# Precision_Leonardo_Charlieplex_2_0.net
KiCad netlist of a schematic drawn in EAGLE
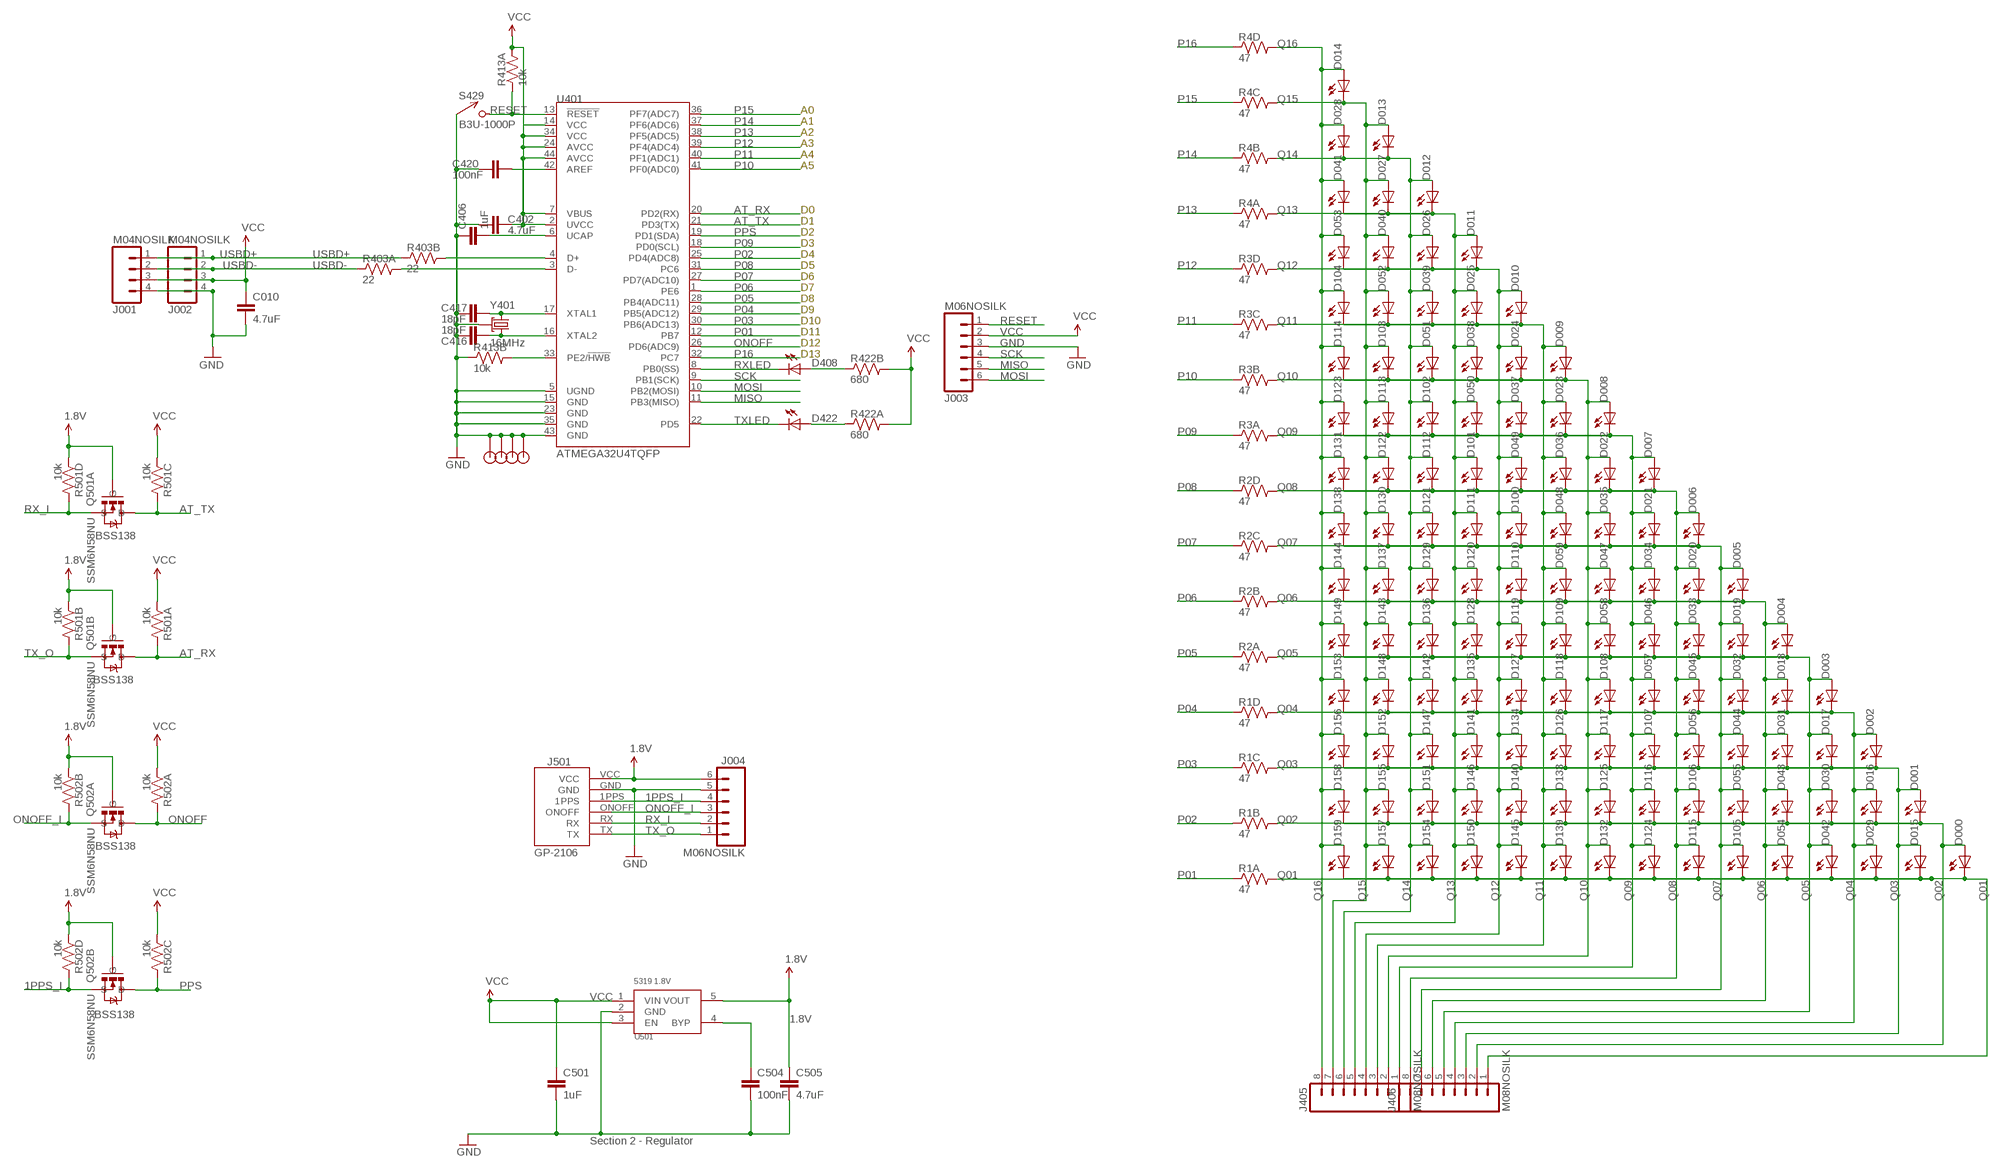
[diagram p0: schematic, sheet 1]

(export (version "E")
  (design (tool "Eeschema 10.0.6"))
  (components
    (comp (ref "C010")
      (value "4.7uF")
      (footprint "eagle-import:0603-CAP")
      (libsource (lib "eagle-import") (part "CAP0603-CAP"))
    )
    (comp (ref "C402")
      (value "4.7uF")
      (footprint "eagle-import:0603-CAP")
      (libsource (lib "eagle-import") (part "CAP0603-CAP"))
    )
    (comp (ref "C406")
      (value "1uF")
      (footprint "eagle-import:0603-CAP")
      (libsource (lib "eagle-import") (part "SparkFun-Passives_CAP0603-CAP"))
    )
    (comp (ref "C416")
      (value "18pF")
      (footprint "eagle-import:0603-CAP")
      (libsource (lib "eagle-import") (part "CAP0603-CAP"))
    )
    (comp (ref "C417")
      (value "18pF")
      (footprint "eagle-import:0603-CAP")
      (libsource (lib "eagle-import") (part "CAP0603-CAP"))
    )
    (comp (ref "C420")
      (value "100nF")
      (footprint "eagle-import:0603-CAP")
      (libsource (lib "eagle-import") (part "CAP0603-CAP"))
    )
    (comp (ref "C501")
      (value "1uF")
      (footprint "eagle-import:0603-CAP")
      (libsource (lib "eagle-import") (part "SparkFun-Passives_CAP0603-CAP"))
    )
    (comp (ref "C504")
      (value "100nF")
      (footprint "eagle-import:0603-CAP")
      (libsource (lib "eagle-import") (part "SparkFun-Passives_CAP0603-CAP"))
    )
    (comp (ref "C505")
      (value "4.7uF")
      (footprint "eagle-import:0603-CAP")
      (libsource (lib "eagle-import") (part "SparkFun-Passives_CAP0603-CAP"))
    )
    (comp (ref "D000")
      (value "HOUR")
      (footprint "eagle-import:LED-0603")
      (libsource (lib "eagle-import") (part "LED0603"))
    )
    (comp (ref "D001")
      (value "HOUR")
      (footprint "eagle-import:LED-0603")
      (libsource (lib "eagle-import") (part "LED0603"))
    )
    (comp (ref "D002")
      (value "HOUR")
      (footprint "eagle-import:LED-0603")
      (libsource (lib "eagle-import") (part "LED0603"))
    )
    (comp (ref "D003")
      (value "HOUR")
      (footprint "eagle-import:LED-0603")
      (libsource (lib "eagle-import") (part "LED0603"))
    )
    (comp (ref "D004")
      (value "HOUR")
      (footprint "eagle-import:LED-0603")
      (libsource (lib "eagle-import") (part "LED0603"))
    )
    (comp (ref "D005")
      (value "HOUR")
      (footprint "eagle-import:LED-0603")
      (libsource (lib "eagle-import") (part "LED0603"))
    )
    (comp (ref "D006")
      (value "HOUR")
      (footprint "eagle-import:LED-0603")
      (libsource (lib "eagle-import") (part "LED0603"))
    )
    (comp (ref "D007")
      (value "HOUR")
      (footprint "eagle-import:LED-0603")
      (libsource (lib "eagle-import") (part "LED0603"))
    )
    (comp (ref "D008")
      (value "HOUR")
      (footprint "eagle-import:LED-0603")
      (libsource (lib "eagle-import") (part "LED0603"))
    )
    (comp (ref "D009")
      (value "HOUR")
      (footprint "eagle-import:LED-0603")
      (libsource (lib "eagle-import") (part "LED0603"))
    )
    (comp (ref "D010")
      (value "HOUR")
      (footprint "eagle-import:LED-0603")
      (libsource (lib "eagle-import") (part "LED0603"))
    )
    (comp (ref "D011")
      (value "HOUR")
      (footprint "eagle-import:LED-0603")
      (libsource (lib "eagle-import") (part "LED0603"))
    )
    (comp (ref "D012")
      (value "HOUR")
      (footprint "eagle-import:LED-0603")
      (libsource (lib "eagle-import") (part "LED0603"))
    )
    (comp (ref "D013")
      (value "HOUR")
      (footprint "eagle-import:LED-0603")
      (libsource (lib "eagle-import") (part "LED0603"))
    )
    (comp (ref "D014")
      (value "HOUR")
      (footprint "eagle-import:LED-0603")
      (libsource (lib "eagle-import") (part "LED0603"))
    )
    (comp (ref "D015")
      (value "HOUR")
      (footprint "eagle-import:LED-0603")
      (libsource (lib "eagle-import") (part "LED0603"))
    )
    (comp (ref "D016")
      (value "HOUR")
      (footprint "eagle-import:LED-0603")
      (libsource (lib "eagle-import") (part "LED0603"))
    )
    (comp (ref "D017")
      (value "HOUR")
      (footprint "eagle-import:LED-0603")
      (libsource (lib "eagle-import") (part "LED0603"))
    )
    (comp (ref "D018")
      (value "HOUR")
      (footprint "eagle-import:LED-0603")
      (libsource (lib "eagle-import") (part "LED0603"))
    )
    (comp (ref "D019")
      (value "HOUR")
      (footprint "eagle-import:LED-0603")
      (libsource (lib "eagle-import") (part "LED0603"))
    )
    (comp (ref "D020")
      (value "HOUR")
      (footprint "eagle-import:LED-0603")
      (libsource (lib "eagle-import") (part "LED0603"))
    )
    (comp (ref "D021")
      (value "HOUR")
      (footprint "eagle-import:LED-0603")
      (libsource (lib "eagle-import") (part "LED0603"))
    )
    (comp (ref "D022")
      (value "HOUR")
      (footprint "eagle-import:LED-0603")
      (libsource (lib "eagle-import") (part "LED0603"))
    )
    (comp (ref "D023")
      (value "HOUR")
      (footprint "eagle-import:LED-0603")
      (libsource (lib "eagle-import") (part "LED0603"))
    )
    (comp (ref "D024")
      (value "HOUR")
      (footprint "eagle-import:LED-0603")
      (libsource (lib "eagle-import") (part "LED0603"))
    )
    (comp (ref "D025")
      (value "HOUR")
      (footprint "eagle-import:LED-0603")
      (libsource (lib "eagle-import") (part "LED0603"))
    )
    (comp (ref "D026")
      (value "HOUR")
      (footprint "eagle-import:LED-0603")
      (libsource (lib "eagle-import") (part "LED0603"))
    )
    (comp (ref "D027")
      (value "HOUR")
      (footprint "eagle-import:LED-0603")
      (libsource (lib "eagle-import") (part "LED0603"))
    )
    (comp (ref "D028")
      (value "HOUR")
      (footprint "eagle-import:LED-0603")
      (libsource (lib "eagle-import") (part "LED0603"))
    )
    (comp (ref "D029")
      (value "HOUR")
      (footprint "eagle-import:LED-0603")
      (libsource (lib "eagle-import") (part "LED0603"))
    )
    (comp (ref "D030")
      (value "HOUR")
      (footprint "eagle-import:LED-0603")
      (libsource (lib "eagle-import") (part "LED0603"))
    )
    (comp (ref "D031")
      (value "HOUR")
      (footprint "eagle-import:LED-0603")
      (libsource (lib "eagle-import") (part "LED0603"))
    )
    (comp (ref "D032")
      (value "HOUR")
      (footprint "eagle-import:LED-0603")
      (libsource (lib "eagle-import") (part "LED0603"))
    )
    (comp (ref "D033")
      (value "HOUR")
      (footprint "eagle-import:LED-0603")
      (libsource (lib "eagle-import") (part "LED0603"))
    )
    (comp (ref "D034")
      (value "HOUR")
      (footprint "eagle-import:LED-0603")
      (libsource (lib "eagle-import") (part "LED0603"))
    )
    (comp (ref "D035")
      (value "HOUR")
      (footprint "eagle-import:LED-0603")
      (libsource (lib "eagle-import") (part "LED0603"))
    )
    (comp (ref "D036")
      (value "HOUR")
      (footprint "eagle-import:LED-0603")
      (libsource (lib "eagle-import") (part "LED0603"))
    )
    (comp (ref "D037")
      (value "HOUR")
      (footprint "eagle-import:LED-0603")
      (libsource (lib "eagle-import") (part "LED0603"))
    )
    (comp (ref "D038")
      (value "HOUR")
      (footprint "eagle-import:LED-0603")
      (libsource (lib "eagle-import") (part "LED0603"))
    )
    (comp (ref "D039")
      (value "HOUR")
      (footprint "eagle-import:LED-0603")
      (libsource (lib "eagle-import") (part "LED0603"))
    )
    (comp (ref "D040")
      (value "HOUR")
      (footprint "eagle-import:LED-0603")
      (libsource (lib "eagle-import") (part "LED0603"))
    )
    (comp (ref "D041")
      (value "HOUR")
      (footprint "eagle-import:LED-0603")
      (libsource (lib "eagle-import") (part "LED0603"))
    )
    (comp (ref "D042")
      (value "HOUR")
      (footprint "eagle-import:LED-0603")
      (libsource (lib "eagle-import") (part "LED0603"))
    )
    (comp (ref "D043")
      (value "HOUR")
      (footprint "eagle-import:LED-0603")
      (libsource (lib "eagle-import") (part "LED0603"))
    )
    (comp (ref "D044")
      (value "HOUR")
      (footprint "eagle-import:LED-0603")
      (libsource (lib "eagle-import") (part "LED0603"))
    )
    (comp (ref "D045")
      (value "HOUR")
      (footprint "eagle-import:LED-0603")
      (libsource (lib "eagle-import") (part "LED0603"))
    )
    (comp (ref "D046")
      (value "HOUR")
      (footprint "eagle-import:LED-0603")
      (libsource (lib "eagle-import") (part "LED0603"))
    )
    (comp (ref "D047")
      (value "HOUR")
      (footprint "eagle-import:LED-0603")
      (libsource (lib "eagle-import") (part "LED0603"))
    )
    (comp (ref "D048")
      (value "HOUR")
      (footprint "eagle-import:LED-0603")
      (libsource (lib "eagle-import") (part "LED0603"))
    )
    (comp (ref "D049")
      (value "HOUR")
      (footprint "eagle-import:LED-0603")
      (libsource (lib "eagle-import") (part "LED0603"))
    )
    (comp (ref "D050")
      (value "HOUR")
      (footprint "eagle-import:LED-0603")
      (libsource (lib "eagle-import") (part "LED0603"))
    )
    (comp (ref "D051")
      (value "HOUR")
      (footprint "eagle-import:LED-0603")
      (libsource (lib "eagle-import") (part "LED0603"))
    )
    (comp (ref "D052")
      (value "HOUR")
      (footprint "eagle-import:LED-0603")
      (libsource (lib "eagle-import") (part "LED0603"))
    )
    (comp (ref "D053")
      (value "HOUR")
      (footprint "eagle-import:LED-0603")
      (libsource (lib "eagle-import") (part "LED0603"))
    )
    (comp (ref "D054")
      (value "HOUR")
      (footprint "eagle-import:LED-0603")
      (libsource (lib "eagle-import") (part "LED0603"))
    )
    (comp (ref "D055")
      (value "HOUR")
      (footprint "eagle-import:LED-0603")
      (libsource (lib "eagle-import") (part "LED0603"))
    )
    (comp (ref "D056")
      (value "HOUR")
      (footprint "eagle-import:LED-0603")
      (libsource (lib "eagle-import") (part "LED0603"))
    )
    (comp (ref "D057")
      (value "HOUR")
      (footprint "eagle-import:LED-0603")
      (libsource (lib "eagle-import") (part "LED0603"))
    )
    (comp (ref "D058")
      (value "HOUR")
      (footprint "eagle-import:LED-0603")
      (libsource (lib "eagle-import") (part "LED0603"))
    )
    (comp (ref "D059")
      (value "HOUR")
      (footprint "eagle-import:LED-0603")
      (libsource (lib "eagle-import") (part "LED0603"))
    )
    (comp (ref "D100")
      (value "HOUR")
      (footprint "eagle-import:LED-0603")
      (libsource (lib "eagle-import") (part "LED0603"))
    )
    (comp (ref "D101")
      (value "HOUR")
      (footprint "eagle-import:LED-0603")
      (libsource (lib "eagle-import") (part "LED0603"))
    )
    (comp (ref "D102")
      (value "HOUR")
      (footprint "eagle-import:LED-0603")
      (libsource (lib "eagle-import") (part "LED0603"))
    )
    (comp (ref "D103")
      (value "HOUR")
      (footprint "eagle-import:LED-0603")
      (libsource (lib "eagle-import") (part "LED0603"))
    )
    (comp (ref "D104")
      (value "HOUR")
      (footprint "eagle-import:LED-0603")
      (libsource (lib "eagle-import") (part "LED0603"))
    )
    (comp (ref "D105")
      (value "HOUR")
      (footprint "eagle-import:LED-0603")
      (libsource (lib "eagle-import") (part "LED0603"))
    )
    (comp (ref "D106")
      (value "HOUR")
      (footprint "eagle-import:LED-0603")
      (libsource (lib "eagle-import") (part "LED0603"))
    )
    (comp (ref "D107")
      (value "HOUR")
      (footprint "eagle-import:LED-0603")
      (libsource (lib "eagle-import") (part "LED0603"))
    )
    (comp (ref "D108")
      (value "HOUR")
      (footprint "eagle-import:LED-0603")
      (libsource (lib "eagle-import") (part "LED0603"))
    )
    (comp (ref "D109")
      (value "HOUR")
      (footprint "eagle-import:LED-0603")
      (libsource (lib "eagle-import") (part "LED0603"))
    )
    (comp (ref "D110")
      (value "HOUR")
      (footprint "eagle-import:LED-0603")
      (libsource (lib "eagle-import") (part "LED0603"))
    )
    (comp (ref "D111")
      (value "HOUR")
      (footprint "eagle-import:LED-0603")
      (libsource (lib "eagle-import") (part "LED0603"))
    )
    (comp (ref "D112")
      (value "HOUR")
      (footprint "eagle-import:LED-0603")
      (libsource (lib "eagle-import") (part "LED0603"))
    )
    (comp (ref "D113")
      (value "HOUR")
      (footprint "eagle-import:LED-0603")
      (libsource (lib "eagle-import") (part "LED0603"))
    )
    (comp (ref "D114")
      (value "HOUR")
      (footprint "eagle-import:LED-0603")
      (libsource (lib "eagle-import") (part "LED0603"))
    )
    (comp (ref "D115")
      (value "HOUR")
      (footprint "eagle-import:LED-0603")
      (libsource (lib "eagle-import") (part "LED0603"))
    )
    (comp (ref "D116")
      (value "HOUR")
      (footprint "eagle-import:LED-0603")
      (libsource (lib "eagle-import") (part "LED0603"))
    )
    (comp (ref "D117")
      (value "HOUR")
      (footprint "eagle-import:LED-0603")
      (libsource (lib "eagle-import") (part "LED0603"))
    )
    (comp (ref "D118")
      (value "HOUR")
      (footprint "eagle-import:LED-0603")
      (libsource (lib "eagle-import") (part "LED0603"))
    )
    (comp (ref "D119")
      (value "HOUR")
      (footprint "eagle-import:LED-0603")
      (libsource (lib "eagle-import") (part "LED0603"))
    )
    (comp (ref "D120")
      (value "HOUR")
      (footprint "eagle-import:LED-0603")
      (libsource (lib "eagle-import") (part "LED0603"))
    )
    (comp (ref "D121")
      (value "HOUR")
      (footprint "eagle-import:LED-0603")
      (libsource (lib "eagle-import") (part "LED0603"))
    )
    (comp (ref "D122")
      (value "HOUR")
      (footprint "eagle-import:LED-0603")
      (libsource (lib "eagle-import") (part "LED0603"))
    )
    (comp (ref "D123")
      (value "HOUR")
      (footprint "eagle-import:LED-0603")
      (libsource (lib "eagle-import") (part "LED0603"))
    )
    (comp (ref "D124")
      (value "HOUR")
      (footprint "eagle-import:LED-0603")
      (libsource (lib "eagle-import") (part "LED0603"))
    )
    (comp (ref "D125")
      (value "HOUR")
      (footprint "eagle-import:LED-0603")
      (libsource (lib "eagle-import") (part "LED0603"))
    )
    (comp (ref "D126")
      (value "HOUR")
      (footprint "eagle-import:LED-0603")
      (libsource (lib "eagle-import") (part "LED0603"))
    )
    (comp (ref "D127")
      (value "HOUR")
      (footprint "eagle-import:LED-0603")
      (libsource (lib "eagle-import") (part "LED0603"))
    )
    (comp (ref "D128")
      (value "HOUR")
      (footprint "eagle-import:LED-0603")
      (libsource (lib "eagle-import") (part "LED0603"))
    )
    (comp (ref "D129")
      (value "HOUR")
      (footprint "eagle-import:LED-0603")
      (libsource (lib "eagle-import") (part "LED0603"))
    )
    (comp (ref "D130")
      (value "HOUR")
      (footprint "eagle-import:LED-0603")
      (libsource (lib "eagle-import") (part "LED0603"))
    )
    (comp (ref "D131")
      (value "HOUR")
      (footprint "eagle-import:LED-0603")
      (libsource (lib "eagle-import") (part "LED0603"))
    )
    (comp (ref "D132")
      (value "HOUR")
      (footprint "eagle-import:LED-0603")
      (libsource (lib "eagle-import") (part "LED0603"))
    )
    (comp (ref "D133")
      (value "HOUR")
      (footprint "eagle-import:LED-0603")
      (libsource (lib "eagle-import") (part "LED0603"))
    )
    (comp (ref "D134")
      (value "HOUR")
      (footprint "eagle-import:LED-0603")
      (libsource (lib "eagle-import") (part "LED0603"))
    )
    (comp (ref "D135")
      (value "HOUR")
      (footprint "eagle-import:LED-0603")
      (libsource (lib "eagle-import") (part "LED0603"))
    )
    (comp (ref "D136")
      (value "HOUR")
      (footprint "eagle-import:LED-0603")
      (libsource (lib "eagle-import") (part "LED0603"))
    )
    (comp (ref "D137")
      (value "HOUR")
      (footprint "eagle-import:LED-0603")
      (libsource (lib "eagle-import") (part "LED0603"))
    )
    (comp (ref "D138")
      (value "HOUR")
      (footprint "eagle-import:LED-0603")
      (libsource (lib "eagle-import") (part "LED0603"))
    )
    (comp (ref "D139")
      (value "HOUR")
      (footprint "eagle-import:LED-0603")
      (libsource (lib "eagle-import") (part "LED0603"))
    )
    (comp (ref "D140")
      (value "HOUR")
      (footprint "eagle-import:LED-0603")
      (libsource (lib "eagle-import") (part "LED0603"))
    )
    (comp (ref "D141")
      (value "HOUR")
      (footprint "eagle-import:LED-0603")
      (libsource (lib "eagle-import") (part "LED0603"))
    )
    (comp (ref "D142")
      (value "HOUR")
      (footprint "eagle-import:LED-0603")
      (libsource (lib "eagle-import") (part "LED0603"))
    )
    (comp (ref "D143")
      (value "HOUR")
      (footprint "eagle-import:LED-0603")
      (libsource (lib "eagle-import") (part "LED0603"))
    )
    (comp (ref "D144")
      (value "HOUR")
      (footprint "eagle-import:LED-0603")
      (libsource (lib "eagle-import") (part "LED0603"))
    )
    (comp (ref "D145")
      (value "HOUR")
      (footprint "eagle-import:LED-0603")
      (libsource (lib "eagle-import") (part "LED0603"))
    )
    (comp (ref "D146")
      (value "HOUR")
      (footprint "eagle-import:LED-0603")
      (libsource (lib "eagle-import") (part "LED0603"))
    )
    (comp (ref "D147")
      (value "HOUR")
      (footprint "eagle-import:LED-0603")
      (libsource (lib "eagle-import") (part "LED0603"))
    )
    (comp (ref "D148")
      (value "HOUR")
      (footprint "eagle-import:LED-0603")
      (libsource (lib "eagle-import") (part "LED0603"))
    )
    (comp (ref "D149")
      (value "HOUR")
      (footprint "eagle-import:LED-0603")
      (libsource (lib "eagle-import") (part "LED0603"))
    )
    (comp (ref "D150")
      (value "HOUR")
      (footprint "eagle-import:LED-0603")
      (libsource (lib "eagle-import") (part "LED0603"))
    )
    (comp (ref "D151")
      (value "HOUR")
      (footprint "eagle-import:LED-0603")
      (libsource (lib "eagle-import") (part "LED0603"))
    )
    (comp (ref "D152")
      (value "HOUR")
      (footprint "eagle-import:LED-0603")
      (libsource (lib "eagle-import") (part "LED0603"))
    )
    (comp (ref "D153")
      (value "HOUR")
      (footprint "eagle-import:LED-0603")
      (libsource (lib "eagle-import") (part "LED0603"))
    )
    (comp (ref "D154")
      (value "HOUR")
      (footprint "eagle-import:LED-0603")
      (libsource (lib "eagle-import") (part "LED0603"))
    )
    (comp (ref "D155")
      (value "HOUR")
      (footprint "eagle-import:LED-0603")
      (libsource (lib "eagle-import") (part "LED0603"))
    )
    (comp (ref "D156")
      (value "HOUR")
      (footprint "eagle-import:LED-0603")
      (libsource (lib "eagle-import") (part "LED0603"))
    )
    (comp (ref "D157")
      (value "HOUR")
      (footprint "eagle-import:LED-0603")
      (libsource (lib "eagle-import") (part "LED0603"))
    )
    (comp (ref "D158")
      (value "HOUR")
      (footprint "eagle-import:LED-0603")
      (libsource (lib "eagle-import") (part "LED0603"))
    )
    (comp (ref "D159")
      (value "HOUR")
      (footprint "eagle-import:LED-0603")
      (libsource (lib "eagle-import") (part "LED0603"))
    )
    (comp (ref "D408")
      (value "RED")
      (footprint "eagle-import:LED-0603")
      (libsource (lib "eagle-import") (part "LED0603"))
    )
    (comp (ref "D422")
      (value "BLUE")
      (footprint "eagle-import:LED-0603")
      (libsource (lib "eagle-import") (part "LED0603"))
    )
    (comp (ref "J001")
      (value "M04NOSILK")
      (footprint "eagle-import:M04SIP")
      (libsource (lib "eagle-import") (part "M04NOSILK"))
    )
    (comp (ref "J002")
      (value "M04NOSILK")
      (footprint "eagle-import:M04SIP")
      (libsource (lib "eagle-import") (part "M04NOSILK"))
    )
    (comp (ref "J003")
      (value "M06NOSILK")
      (footprint "eagle-import:M06SIP")
      (libsource (lib "eagle-import") (part "M06NOSILK"))
    )
    (comp (ref "J004")
      (value "M06NOSILK")
      (footprint "eagle-import:M06SIP")
      (libsource (lib "eagle-import") (part "M06NOSILK"))
    )
    (comp (ref "J405")
      (value "M08NOSILK")
      (footprint "eagle-import:M08SIP")
      (libsource (lib "eagle-import") (part "M08NOSILK"))
    )
    (comp (ref "J406")
      (value "M08NOSILK")
      (footprint "eagle-import:M08SIP")
      (libsource (lib "eagle-import") (part "M08NOSILK"))
    )
    (comp (ref "J501")
      (value "GP-2106")
      (footprint "eagle-import:GP-2106")
      (libsource (lib "eagle-import") (part "GP-2106"))
    )
    (comp (ref "JP1")
      (value "STANDOFF")
      (footprint "eagle-import:STANDOFF")
      (libsource (lib "eagle-import") (part "STANDOFF"))
    )
    (comp (ref "JP2")
      (value "STANDOFF")
      (footprint "eagle-import:STANDOFF")
      (libsource (lib "eagle-import") (part "STANDOFF"))
    )
    (comp (ref "JP3")
      (value "STANDOFF")
      (footprint "eagle-import:STANDOFF")
      (libsource (lib "eagle-import") (part "STANDOFF"))
    )
    (comp (ref "JP4")
      (value "STANDOFF")
      (footprint "eagle-import:STANDOFF")
      (libsource (lib "eagle-import") (part "STANDOFF"))
    )
    (comp (ref "Q501")
      (value "SSM6N58NU")
      (footprint "eagle-import:UDFN6")
      (libsource (lib "eagle-import") (part "SSM6N58NU"))
    )
    (comp (ref "Q502")
      (value "SSM6N58NU")
      (footprint "eagle-import:UDFN6")
      (libsource (lib "eagle-import") (part "SSM6N58NU"))
    )
    (comp (ref "R1")
      (value "47")
      (footprint "eagle-import:CRA04")
      (libsource (lib "eagle-import") (part "RP404"))
    )
    (comp (ref "R2")
      (value "47")
      (footprint "eagle-import:CRA04")
      (libsource (lib "eagle-import") (part "RP404"))
    )
    (comp (ref "R3")
      (value "47")
      (footprint "eagle-import:CRA04")
      (libsource (lib "eagle-import") (part "RP404"))
    )
    (comp (ref "R4")
      (value "47")
      (footprint "eagle-import:CRA04")
      (libsource (lib "eagle-import") (part "RP404"))
    )
    (comp (ref "R403")
      (value "22")
      (footprint "eagle-import:CRA02")
      (libsource (lib "eagle-import") (part "RP2EXB24V"))
    )
    (comp (ref "R413")
      (value "10k")
      (footprint "eagle-import:CRA02")
      (libsource (lib "eagle-import") (part "RP2EXB24V"))
    )
    (comp (ref "R422")
      (value "680")
      (footprint "eagle-import:CRA02")
      (libsource (lib "eagle-import") (part "RP2EXB24V"))
    )
    (comp (ref "R501")
      (value "10k")
      (footprint "eagle-import:CRA04")
      (fields (field (name "DIGIKEY") "CRA4S810KCT-ND"))
      (libsource (lib "eagle-import") (part "RP404"))
    )
    (comp (ref "R502")
      (value "10k")
      (footprint "eagle-import:CRA04")
      (fields (field (name "DIGIKEY") "CRA4S810KCT-ND"))
      (libsource (lib "eagle-import") (part "RP404"))
    )
    (comp (ref "S429")
      (value "B3U-1000P")
      (footprint "eagle-import:B3U-1000P")
      (libsource (lib "eagle-import") (part "B3U-1000P"))
    )
    (comp (ref "U401")
      (value "ATMEGA32U4TQFP")
      (footprint "eagle-import:SPARKFUN-DIGITALIC_TQFP44")
      (libsource (lib "eagle-import") (part "ATMEGA32U4TQFP"))
    )
    (comp (ref "U501")
      (value "5319 1.8V")
      (footprint "eagle-import:SOT-23-5")
      (libsource (lib "eagle-import") (part "MIC5319D5"))
    )
    (comp (ref "Y401")
      (value "16MHz")
      (footprint "eagle-import:CRYSTAL_SMD")
      (libsource (lib "eagle-import") (part "TSX-3225"))
    )
  )
  (nets
    (net (code "1") (name "/1PPS_I") (class "Default")
      (node (ref "J004") (pin "4") (pinfunction "4_4") (pintype "passive"))
      (node (ref "J501") (pin "1PPS") (pinfunction "1PPS_1PPS") (pintype "bidirectional"))
      (node (ref "Q502") (pin "4") (pinfunction "S_4") (pintype "passive"))
      (node (ref "R502") (pin "5") (pinfunction "2_5") (pintype "passive"))
    )
    (net (code "2") (name "/AT_RX") (class "Default")
      (node (ref "Q501") (pin "3") (pinfunction "D_3") (pintype "passive"))
      (node (ref "R501") (pin "8") (pinfunction "2_8") (pintype "passive"))
      (node (ref "U401") (pin "20") (pinfunction "PD2(RX)_20") (pintype "bidirectional"))
    )
    (net (code "3") (name "/AT_TX") (class "Default")
      (node (ref "Q501") (pin "6") (pinfunction "D_6") (pintype "passive"))
      (node (ref "R501") (pin "6") (pinfunction "2_6") (pintype "passive"))
      (node (ref "U401") (pin "21") (pinfunction "PD3(TX)_21") (pintype "bidirectional"))
    )
    (net (code "4") (name "/MISO") (class "Default")
      (node (ref "J003") (pin "5") (pinfunction "5_5") (pintype "passive"))
      (node (ref "U401") (pin "11") (pinfunction "PB3(MISO)_11") (pintype "bidirectional"))
    )
    (net (code "5") (name "/MOSI") (class "Default")
      (node (ref "J003") (pin "6") (pinfunction "6_6") (pintype "passive"))
      (node (ref "U401") (pin "10") (pinfunction "PB2(MOSI)_10") (pintype "bidirectional"))
    )
    (net (code "6") (name "/ONOFF") (class "Default")
      (node (ref "Q502") (pin "6") (pinfunction "D_6") (pintype "passive"))
      (node (ref "R502") (pin "8") (pinfunction "2_8") (pintype "passive"))
      (node (ref "U401") (pin "26") (pinfunction "PD6(ADC9)_26") (pintype "bidirectional"))
    )
    (net (code "7") (name "/ONOFF_I") (class "Default")
      (node (ref "J004") (pin "3") (pinfunction "3_3") (pintype "passive"))
      (node (ref "J501") (pin "ONOFF") (pinfunction "ONOFF_ONOFF") (pintype "bidirectional"))
      (node (ref "Q502") (pin "1") (pinfunction "S_1") (pintype "passive"))
      (node (ref "R502") (pin "7") (pinfunction "2_7") (pintype "passive"))
    )
    (net (code "8") (name "/P01") (class "Default")
      (node (ref "R1") (pin "1") (pinfunction "1_1") (pintype "passive"))
      (node (ref "U401") (pin "12") (pinfunction "PB7_12") (pintype "bidirectional"))
    )
    (net (code "9") (name "/P02") (class "Default")
      (node (ref "R1") (pin "2") (pinfunction "1_2") (pintype "passive"))
      (node (ref "U401") (pin "25") (pinfunction "PD4(ADC8)_25") (pintype "bidirectional"))
    )
    (net (code "10") (name "/P03") (class "Default")
      (node (ref "R1") (pin "3") (pinfunction "1_3") (pintype "passive"))
      (node (ref "U401") (pin "30") (pinfunction "PB6(ADC13)_30") (pintype "bidirectional"))
    )
    (net (code "11") (name "/P04") (class "Default")
      (node (ref "R1") (pin "4") (pinfunction "1_4") (pintype "passive"))
      (node (ref "U401") (pin "29") (pinfunction "PB5(ADC12)_29") (pintype "bidirectional"))
    )
    (net (code "12") (name "/P05") (class "Default")
      (node (ref "R2") (pin "1") (pinfunction "1_1") (pintype "passive"))
      (node (ref "U401") (pin "28") (pinfunction "PB4(ADC11)_28") (pintype "bidirectional"))
    )
    (net (code "13") (name "/P06") (class "Default")
      (node (ref "R2") (pin "2") (pinfunction "1_2") (pintype "passive"))
      (node (ref "U401") (pin "1") (pinfunction "PE6_1") (pintype "bidirectional"))
    )
    (net (code "14") (name "/P07") (class "Default")
      (node (ref "R2") (pin "3") (pinfunction "1_3") (pintype "passive"))
      (node (ref "U401") (pin "27") (pinfunction "PD7(ADC10)_27") (pintype "bidirectional"))
    )
    (net (code "15") (name "/P08") (class "Default")
      (node (ref "R2") (pin "4") (pinfunction "1_4") (pintype "passive"))
      (node (ref "U401") (pin "31") (pinfunction "PC6_31") (pintype "bidirectional"))
    )
    (net (code "16") (name "/P09") (class "Default")
      (node (ref "R3") (pin "1") (pinfunction "1_1") (pintype "passive"))
      (node (ref "U401") (pin "18") (pinfunction "PD0(SCL)_18") (pintype "bidirectional"))
    )
    (net (code "17") (name "/P10") (class "Default")
      (node (ref "R3") (pin "2") (pinfunction "1_2") (pintype "passive"))
      (node (ref "U401") (pin "41") (pinfunction "PF0(ADC0)_41") (pintype "bidirectional"))
    )
    (net (code "18") (name "/P11") (class "Default")
      (node (ref "R3") (pin "3") (pinfunction "1_3") (pintype "passive"))
      (node (ref "U401") (pin "40") (pinfunction "PF1(ADC1)_40") (pintype "bidirectional"))
    )
    (net (code "19") (name "/P12") (class "Default")
      (node (ref "R3") (pin "4") (pinfunction "1_4") (pintype "passive"))
      (node (ref "U401") (pin "39") (pinfunction "PF4(ADC4)_39") (pintype "bidirectional"))
    )
    (net (code "20") (name "/P13") (class "Default")
      (node (ref "R4") (pin "1") (pinfunction "1_1") (pintype "passive"))
      (node (ref "U401") (pin "38") (pinfunction "PF5(ADC5)_38") (pintype "bidirectional"))
    )
    (net (code "21") (name "/P14") (class "Default")
      (node (ref "R4") (pin "2") (pinfunction "1_2") (pintype "passive"))
      (node (ref "U401") (pin "37") (pinfunction "PF6(ADC6)_37") (pintype "bidirectional"))
    )
    (net (code "22") (name "/P15") (class "Default")
      (node (ref "R4") (pin "3") (pinfunction "1_3") (pintype "passive"))
      (node (ref "U401") (pin "36") (pinfunction "PF7(ADC7)_36") (pintype "bidirectional"))
    )
    (net (code "23") (name "/P16") (class "Default")
      (node (ref "R4") (pin "4") (pinfunction "1_4") (pintype "passive"))
      (node (ref "U401") (pin "32") (pinfunction "PC7_32") (pintype "bidirectional"))
    )
    (net (code "24") (name "/PPS") (class "Default")
      (node (ref "Q502") (pin "3") (pinfunction "D_3") (pintype "passive"))
      (node (ref "R502") (pin "6") (pinfunction "2_6") (pintype "passive"))
      (node (ref "U401") (pin "19") (pinfunction "PD1(SDA)_19") (pintype "bidirectional"))
    )
    (net (code "25") (name "/Q01") (class "Default")
      (node (ref "D000") (pin "C") (pinfunction "C_C") (pintype "passive"))
      (node (ref "D015") (pin "C") (pinfunction "C_C") (pintype "passive"))
      (node (ref "D029") (pin "C") (pinfunction "C_C") (pintype "passive"))
      (node (ref "D042") (pin "C") (pinfunction "C_C") (pintype "passive"))
      (node (ref "D054") (pin "C") (pinfunction "C_C") (pintype "passive"))
      (node (ref "D105") (pin "C") (pinfunction "C_C") (pintype "passive"))
      (node (ref "D115") (pin "C") (pinfunction "C_C") (pintype "passive"))
      (node (ref "D124") (pin "C") (pinfunction "C_C") (pintype "passive"))
      (node (ref "D132") (pin "C") (pinfunction "C_C") (pintype "passive"))
      (node (ref "D139") (pin "C") (pinfunction "C_C") (pintype "passive"))
      (node (ref "D145") (pin "C") (pinfunction "C_C") (pintype "passive"))
      (node (ref "D150") (pin "C") (pinfunction "C_C") (pintype "passive"))
      (node (ref "D154") (pin "C") (pinfunction "C_C") (pintype "passive"))
      (node (ref "D157") (pin "C") (pinfunction "C_C") (pintype "passive"))
      (node (ref "D159") (pin "C") (pinfunction "C_C") (pintype "passive"))
      (node (ref "J406") (pin "1") (pinfunction "1_1") (pintype "passive"))
      (node (ref "R1") (pin "8") (pinfunction "2_8") (pintype "passive"))
    )
    (net (code "26") (name "/Q02") (class "Default")
      (node (ref "D000") (pin "A") (pinfunction "A_A") (pintype "passive"))
      (node (ref "D001") (pin "C") (pinfunction "C_C") (pintype "passive"))
      (node (ref "D016") (pin "C") (pinfunction "C_C") (pintype "passive"))
      (node (ref "D030") (pin "C") (pinfunction "C_C") (pintype "passive"))
      (node (ref "D043") (pin "C") (pinfunction "C_C") (pintype "passive"))
      (node (ref "D055") (pin "C") (pinfunction "C_C") (pintype "passive"))
      (node (ref "D106") (pin "C") (pinfunction "C_C") (pintype "passive"))
      (node (ref "D116") (pin "C") (pinfunction "C_C") (pintype "passive"))
      (node (ref "D125") (pin "C") (pinfunction "C_C") (pintype "passive"))
      (node (ref "D133") (pin "C") (pinfunction "C_C") (pintype "passive"))
      (node (ref "D140") (pin "C") (pinfunction "C_C") (pintype "passive"))
      (node (ref "D146") (pin "C") (pinfunction "C_C") (pintype "passive"))
      (node (ref "D151") (pin "C") (pinfunction "C_C") (pintype "passive"))
      (node (ref "D155") (pin "C") (pinfunction "C_C") (pintype "passive"))
      (node (ref "D158") (pin "C") (pinfunction "C_C") (pintype "passive"))
      (node (ref "J406") (pin "2") (pinfunction "2_2") (pintype "passive"))
      (node (ref "R1") (pin "7") (pinfunction "2_7") (pintype "passive"))
    )
    (net (code "27") (name "/Q03") (class "Default")
      (node (ref "D001") (pin "A") (pinfunction "A_A") (pintype "passive"))
      (node (ref "D002") (pin "C") (pinfunction "C_C") (pintype "passive"))
      (node (ref "D015") (pin "A") (pinfunction "A_A") (pintype "passive"))
      (node (ref "D017") (pin "C") (pinfunction "C_C") (pintype "passive"))
      (node (ref "D031") (pin "C") (pinfunction "C_C") (pintype "passive"))
      (node (ref "D044") (pin "C") (pinfunction "C_C") (pintype "passive"))
      (node (ref "D056") (pin "C") (pinfunction "C_C") (pintype "passive"))
      (node (ref "D107") (pin "C") (pinfunction "C_C") (pintype "passive"))
      (node (ref "D117") (pin "C") (pinfunction "C_C") (pintype "passive"))
      (node (ref "D126") (pin "C") (pinfunction "C_C") (pintype "passive"))
      (node (ref "D134") (pin "C") (pinfunction "C_C") (pintype "passive"))
      (node (ref "D141") (pin "C") (pinfunction "C_C") (pintype "passive"))
      (node (ref "D147") (pin "C") (pinfunction "C_C") (pintype "passive"))
      (node (ref "D152") (pin "C") (pinfunction "C_C") (pintype "passive"))
      (node (ref "D156") (pin "C") (pinfunction "C_C") (pintype "passive"))
      (node (ref "J406") (pin "3") (pinfunction "3_3") (pintype "passive"))
      (node (ref "R1") (pin "6") (pinfunction "2_6") (pintype "passive"))
    )
    (net (code "28") (name "/Q04") (class "Default")
      (node (ref "D002") (pin "A") (pinfunction "A_A") (pintype "passive"))
      (node (ref "D003") (pin "C") (pinfunction "C_C") (pintype "passive"))
      (node (ref "D016") (pin "A") (pinfunction "A_A") (pintype "passive"))
      (node (ref "D018") (pin "C") (pinfunction "C_C") (pintype "passive"))
      (node (ref "D029") (pin "A") (pinfunction "A_A") (pintype "passive"))
      (node (ref "D032") (pin "C") (pinfunction "C_C") (pintype "passive"))
      (node (ref "D045") (pin "C") (pinfunction "C_C") (pintype "passive"))
      (node (ref "D057") (pin "C") (pinfunction "C_C") (pintype "passive"))
      (node (ref "D108") (pin "C") (pinfunction "C_C") (pintype "passive"))
      (node (ref "D118") (pin "C") (pinfunction "C_C") (pintype "passive"))
      (node (ref "D127") (pin "C") (pinfunction "C_C") (pintype "passive"))
      (node (ref "D135") (pin "C") (pinfunction "C_C") (pintype "passive"))
      (node (ref "D142") (pin "C") (pinfunction "C_C") (pintype "passive"))
      (node (ref "D148") (pin "C") (pinfunction "C_C") (pintype "passive"))
      (node (ref "D153") (pin "C") (pinfunction "C_C") (pintype "passive"))
      (node (ref "J406") (pin "4") (pinfunction "4_4") (pintype "passive"))
      (node (ref "R1") (pin "5") (pinfunction "2_5") (pintype "passive"))
    )
    (net (code "29") (name "/Q05") (class "Default")
      (node (ref "D003") (pin "A") (pinfunction "A_A") (pintype "passive"))
      (node (ref "D004") (pin "C") (pinfunction "C_C") (pintype "passive"))
      (node (ref "D017") (pin "A") (pinfunction "A_A") (pintype "passive"))
      (node (ref "D019") (pin "C") (pinfunction "C_C") (pintype "passive"))
      (node (ref "D030") (pin "A") (pinfunction "A_A") (pintype "passive"))
      (node (ref "D033") (pin "C") (pinfunction "C_C") (pintype "passive"))
      (node (ref "D042") (pin "A") (pinfunction "A_A") (pintype "passive"))
      (node (ref "D046") (pin "C") (pinfunction "C_C") (pintype "passive"))
      (node (ref "D058") (pin "C") (pinfunction "C_C") (pintype "passive"))
      (node (ref "D109") (pin "C") (pinfunction "C_C") (pintype "passive"))
      (node (ref "D119") (pin "C") (pinfunction "C_C") (pintype "passive"))
      (node (ref "D128") (pin "C") (pinfunction "C_C") (pintype "passive"))
      (node (ref "D136") (pin "C") (pinfunction "C_C") (pintype "passive"))
      (node (ref "D143") (pin "C") (pinfunction "C_C") (pintype "passive"))
      (node (ref "D149") (pin "C") (pinfunction "C_C") (pintype "passive"))
      (node (ref "J406") (pin "5") (pinfunction "5_5") (pintype "passive"))
      (node (ref "R2") (pin "8") (pinfunction "2_8") (pintype "passive"))
    )
    (net (code "30") (name "/Q06") (class "Default")
      (node (ref "D004") (pin "A") (pinfunction "A_A") (pintype "passive"))
      (node (ref "D005") (pin "C") (pinfunction "C_C") (pintype "passive"))
      (node (ref "D018") (pin "A") (pinfunction "A_A") (pintype "passive"))
      (node (ref "D020") (pin "C") (pinfunction "C_C") (pintype "passive"))
      (node (ref "D031") (pin "A") (pinfunction "A_A") (pintype "passive"))
      (node (ref "D034") (pin "C") (pinfunction "C_C") (pintype "passive"))
      (node (ref "D043") (pin "A") (pinfunction "A_A") (pintype "passive"))
      (node (ref "D047") (pin "C") (pinfunction "C_C") (pintype "passive"))
      (node (ref "D054") (pin "A") (pinfunction "A_A") (pintype "passive"))
      (node (ref "D059") (pin "C") (pinfunction "C_C") (pintype "passive"))
      (node (ref "D110") (pin "C") (pinfunction "C_C") (pintype "passive"))
      (node (ref "D120") (pin "C") (pinfunction "C_C") (pintype "passive"))
      (node (ref "D129") (pin "C") (pinfunction "C_C") (pintype "passive"))
      (node (ref "D137") (pin "C") (pinfunction "C_C") (pintype "passive"))
      (node (ref "D144") (pin "C") (pinfunction "C_C") (pintype "passive"))
      (node (ref "J406") (pin "6") (pinfunction "6_6") (pintype "passive"))
      (node (ref "R2") (pin "7") (pinfunction "2_7") (pintype "passive"))
    )
    (net (code "31") (name "/Q07") (class "Default")
      (node (ref "D005") (pin "A") (pinfunction "A_A") (pintype "passive"))
      (node (ref "D006") (pin "C") (pinfunction "C_C") (pintype "passive"))
      (node (ref "D019") (pin "A") (pinfunction "A_A") (pintype "passive"))
      (node (ref "D021") (pin "C") (pinfunction "C_C") (pintype "passive"))
      (node (ref "D032") (pin "A") (pinfunction "A_A") (pintype "passive"))
      (node (ref "D035") (pin "C") (pinfunction "C_C") (pintype "passive"))
      (node (ref "D044") (pin "A") (pinfunction "A_A") (pintype "passive"))
      (node (ref "D048") (pin "C") (pinfunction "C_C") (pintype "passive"))
      (node (ref "D055") (pin "A") (pinfunction "A_A") (pintype "passive"))
      (node (ref "D100") (pin "C") (pinfunction "C_C") (pintype "passive"))
      (node (ref "D105") (pin "A") (pinfunction "A_A") (pintype "passive"))
      (node (ref "D111") (pin "C") (pinfunction "C_C") (pintype "passive"))
      (node (ref "D121") (pin "C") (pinfunction "C_C") (pintype "passive"))
      (node (ref "D130") (pin "C") (pinfunction "C_C") (pintype "passive"))
      (node (ref "D138") (pin "C") (pinfunction "C_C") (pintype "passive"))
      (node (ref "J406") (pin "7") (pinfunction "7_7") (pintype "passive"))
      (node (ref "R2") (pin "6") (pinfunction "2_6") (pintype "passive"))
    )
    (net (code "32") (name "/Q08") (class "Default")
      (node (ref "D006") (pin "A") (pinfunction "A_A") (pintype "passive"))
      (node (ref "D007") (pin "C") (pinfunction "C_C") (pintype "passive"))
      (node (ref "D020") (pin "A") (pinfunction "A_A") (pintype "passive"))
      (node (ref "D022") (pin "C") (pinfunction "C_C") (pintype "passive"))
      (node (ref "D033") (pin "A") (pinfunction "A_A") (pintype "passive"))
      (node (ref "D036") (pin "C") (pinfunction "C_C") (pintype "passive"))
      (node (ref "D045") (pin "A") (pinfunction "A_A") (pintype "passive"))
      (node (ref "D049") (pin "C") (pinfunction "C_C") (pintype "passive"))
      (node (ref "D056") (pin "A") (pinfunction "A_A") (pintype "passive"))
      (node (ref "D101") (pin "C") (pinfunction "C_C") (pintype "passive"))
      (node (ref "D106") (pin "A") (pinfunction "A_A") (pintype "passive"))
      (node (ref "D112") (pin "C") (pinfunction "C_C") (pintype "passive"))
      (node (ref "D115") (pin "A") (pinfunction "A_A") (pintype "passive"))
      (node (ref "D122") (pin "C") (pinfunction "C_C") (pintype "passive"))
      (node (ref "D131") (pin "C") (pinfunction "C_C") (pintype "passive"))
      (node (ref "J406") (pin "8") (pinfunction "8_8") (pintype "passive"))
      (node (ref "R2") (pin "5") (pinfunction "2_5") (pintype "passive"))
    )
    (net (code "33") (name "/Q09") (class "Default")
      (node (ref "D007") (pin "A") (pinfunction "A_A") (pintype "passive"))
      (node (ref "D008") (pin "C") (pinfunction "C_C") (pintype "passive"))
      (node (ref "D021") (pin "A") (pinfunction "A_A") (pintype "passive"))
      (node (ref "D023") (pin "C") (pinfunction "C_C") (pintype "passive"))
      (node (ref "D034") (pin "A") (pinfunction "A_A") (pintype "passive"))
      (node (ref "D037") (pin "C") (pinfunction "C_C") (pintype "passive"))
      (node (ref "D046") (pin "A") (pinfunction "A_A") (pintype "passive"))
      (node (ref "D050") (pin "C") (pinfunction "C_C") (pintype "passive"))
      (node (ref "D057") (pin "A") (pinfunction "A_A") (pintype "passive"))
      (node (ref "D102") (pin "C") (pinfunction "C_C") (pintype "passive"))
      (node (ref "D107") (pin "A") (pinfunction "A_A") (pintype "passive"))
      (node (ref "D113") (pin "C") (pinfunction "C_C") (pintype "passive"))
      (node (ref "D116") (pin "A") (pinfunction "A_A") (pintype "passive"))
      (node (ref "D123") (pin "C") (pinfunction "C_C") (pintype "passive"))
      (node (ref "D124") (pin "A") (pinfunction "A_A") (pintype "passive"))
      (node (ref "J405") (pin "1") (pinfunction "1_1") (pintype "passive"))
      (node (ref "R3") (pin "8") (pinfunction "2_8") (pintype "passive"))
    )
    (net (code "34") (name "/Q10") (class "Default")
      (node (ref "D008") (pin "A") (pinfunction "A_A") (pintype "passive"))
      (node (ref "D009") (pin "C") (pinfunction "C_C") (pintype "passive"))
      (node (ref "D022") (pin "A") (pinfunction "A_A") (pintype "passive"))
      (node (ref "D024") (pin "C") (pinfunction "C_C") (pintype "passive"))
      (node (ref "D035") (pin "A") (pinfunction "A_A") (pintype "passive"))
      (node (ref "D038") (pin "C") (pinfunction "C_C") (pintype "passive"))
      (node (ref "D047") (pin "A") (pinfunction "A_A") (pintype "passive"))
      (node (ref "D051") (pin "C") (pinfunction "C_C") (pintype "passive"))
      (node (ref "D058") (pin "A") (pinfunction "A_A") (pintype "passive"))
      (node (ref "D103") (pin "C") (pinfunction "C_C") (pintype "passive"))
      (node (ref "D108") (pin "A") (pinfunction "A_A") (pintype "passive"))
      (node (ref "D114") (pin "C") (pinfunction "C_C") (pintype "passive"))
      (node (ref "D117") (pin "A") (pinfunction "A_A") (pintype "passive"))
      (node (ref "D125") (pin "A") (pinfunction "A_A") (pintype "passive"))
      (node (ref "D132") (pin "A") (pinfunction "A_A") (pintype "passive"))
      (node (ref "J405") (pin "2") (pinfunction "2_2") (pintype "passive"))
      (node (ref "R3") (pin "7") (pinfunction "2_7") (pintype "passive"))
    )
    (net (code "35") (name "/Q11") (class "Default")
      (node (ref "D009") (pin "A") (pinfunction "A_A") (pintype "passive"))
      (node (ref "D010") (pin "C") (pinfunction "C_C") (pintype "passive"))
      (node (ref "D023") (pin "A") (pinfunction "A_A") (pintype "passive"))
      (node (ref "D025") (pin "C") (pinfunction "C_C") (pintype "passive"))
      (node (ref "D036") (pin "A") (pinfunction "A_A") (pintype "passive"))
      (node (ref "D039") (pin "C") (pinfunction "C_C") (pintype "passive"))
      (node (ref "D048") (pin "A") (pinfunction "A_A") (pintype "passive"))
      (node (ref "D052") (pin "C") (pinfunction "C_C") (pintype "passive"))
      (node (ref "D059") (pin "A") (pinfunction "A_A") (pintype "passive"))
      (node (ref "D104") (pin "C") (pinfunction "C_C") (pintype "passive"))
      (node (ref "D109") (pin "A") (pinfunction "A_A") (pintype "passive"))
      (node (ref "D118") (pin "A") (pinfunction "A_A") (pintype "passive"))
      (node (ref "D126") (pin "A") (pinfunction "A_A") (pintype "passive"))
      (node (ref "D133") (pin "A") (pinfunction "A_A") (pintype "passive"))
      (node (ref "D139") (pin "A") (pinfunction "A_A") (pintype "passive"))
      (node (ref "J405") (pin "3") (pinfunction "3_3") (pintype "passive"))
      (node (ref "R3") (pin "6") (pinfunction "2_6") (pintype "passive"))
    )
    (net (code "36") (name "/Q12") (class "Default")
      (node (ref "D010") (pin "A") (pinfunction "A_A") (pintype "passive"))
      (node (ref "D011") (pin "C") (pinfunction "C_C") (pintype "passive"))
      (node (ref "D024") (pin "A") (pinfunction "A_A") (pintype "passive"))
      (node (ref "D026") (pin "C") (pinfunction "C_C") (pintype "passive"))
      (node (ref "D037") (pin "A") (pinfunction "A_A") (pintype "passive"))
      (node (ref "D040") (pin "C") (pinfunction "C_C") (pintype "passive"))
      (node (ref "D049") (pin "A") (pinfunction "A_A") (pintype "passive"))
      (node (ref "D053") (pin "C") (pinfunction "C_C") (pintype "passive"))
      (node (ref "D100") (pin "A") (pinfunction "A_A") (pintype "passive"))
      (node (ref "D110") (pin "A") (pinfunction "A_A") (pintype "passive"))
      (node (ref "D119") (pin "A") (pinfunction "A_A") (pintype "passive"))
      (node (ref "D127") (pin "A") (pinfunction "A_A") (pintype "passive"))
      (node (ref "D134") (pin "A") (pinfunction "A_A") (pintype "passive"))
      (node (ref "D140") (pin "A") (pinfunction "A_A") (pintype "passive"))
      (node (ref "D145") (pin "A") (pinfunction "A_A") (pintype "passive"))
      (node (ref "J405") (pin "4") (pinfunction "4_4") (pintype "passive"))
      (node (ref "R3") (pin "5") (pinfunction "2_5") (pintype "passive"))
    )
    (net (code "37") (name "/Q13") (class "Default")
      (node (ref "D011") (pin "A") (pinfunction "A_A") (pintype "passive"))
      (node (ref "D012") (pin "C") (pinfunction "C_C") (pintype "passive"))
      (node (ref "D025") (pin "A") (pinfunction "A_A") (pintype "passive"))
      (node (ref "D027") (pin "C") (pinfunction "C_C") (pintype "passive"))
      (node (ref "D038") (pin "A") (pinfunction "A_A") (pintype "passive"))
      (node (ref "D041") (pin "C") (pinfunction "C_C") (pintype "passive"))
      (node (ref "D050") (pin "A") (pinfunction "A_A") (pintype "passive"))
      (node (ref "D101") (pin "A") (pinfunction "A_A") (pintype "passive"))
      (node (ref "D111") (pin "A") (pinfunction "A_A") (pintype "passive"))
      (node (ref "D120") (pin "A") (pinfunction "A_A") (pintype "passive"))
      (node (ref "D128") (pin "A") (pinfunction "A_A") (pintype "passive"))
      (node (ref "D135") (pin "A") (pinfunction "A_A") (pintype "passive"))
      (node (ref "D141") (pin "A") (pinfunction "A_A") (pintype "passive"))
      (node (ref "D146") (pin "A") (pinfunction "A_A") (pintype "passive"))
      (node (ref "D150") (pin "A") (pinfunction "A_A") (pintype "passive"))
      (node (ref "J405") (pin "5") (pinfunction "5_5") (pintype "passive"))
      (node (ref "R4") (pin "8") (pinfunction "2_8") (pintype "passive"))
    )
    (net (code "38") (name "/Q14") (class "Default")
      (node (ref "D012") (pin "A") (pinfunction "A_A") (pintype "passive"))
      (node (ref "D013") (pin "C") (pinfunction "C_C") (pintype "passive"))
      (node (ref "D026") (pin "A") (pinfunction "A_A") (pintype "passive"))
      (node (ref "D028") (pin "C") (pinfunction "C_C") (pintype "passive"))
      (node (ref "D039") (pin "A") (pinfunction "A_A") (pintype "passive"))
      (node (ref "D051") (pin "A") (pinfunction "A_A") (pintype "passive"))
      (node (ref "D102") (pin "A") (pinfunction "A_A") (pintype "passive"))
      (node (ref "D112") (pin "A") (pinfunction "A_A") (pintype "passive"))
      (node (ref "D121") (pin "A") (pinfunction "A_A") (pintype "passive"))
      (node (ref "D129") (pin "A") (pinfunction "A_A") (pintype "passive"))
      (node (ref "D136") (pin "A") (pinfunction "A_A") (pintype "passive"))
      (node (ref "D142") (pin "A") (pinfunction "A_A") (pintype "passive"))
      (node (ref "D147") (pin "A") (pinfunction "A_A") (pintype "passive"))
      (node (ref "D151") (pin "A") (pinfunction "A_A") (pintype "passive"))
      (node (ref "D154") (pin "A") (pinfunction "A_A") (pintype "passive"))
      (node (ref "J405") (pin "6") (pinfunction "6_6") (pintype "passive"))
      (node (ref "R4") (pin "7") (pinfunction "2_7") (pintype "passive"))
    )
    (net (code "39") (name "/Q15") (class "Default")
      (node (ref "D013") (pin "A") (pinfunction "A_A") (pintype "passive"))
      (node (ref "D014") (pin "C") (pinfunction "C_C") (pintype "passive"))
      (node (ref "D027") (pin "A") (pinfunction "A_A") (pintype "passive"))
      (node (ref "D040") (pin "A") (pinfunction "A_A") (pintype "passive"))
      (node (ref "D052") (pin "A") (pinfunction "A_A") (pintype "passive"))
      (node (ref "D103") (pin "A") (pinfunction "A_A") (pintype "passive"))
      (node (ref "D113") (pin "A") (pinfunction "A_A") (pintype "passive"))
      (node (ref "D122") (pin "A") (pinfunction "A_A") (pintype "passive"))
      (node (ref "D130") (pin "A") (pinfunction "A_A") (pintype "passive"))
      (node (ref "D137") (pin "A") (pinfunction "A_A") (pintype "passive"))
      (node (ref "D143") (pin "A") (pinfunction "A_A") (pintype "passive"))
      (node (ref "D148") (pin "A") (pinfunction "A_A") (pintype "passive"))
      (node (ref "D152") (pin "A") (pinfunction "A_A") (pintype "passive"))
      (node (ref "D155") (pin "A") (pinfunction "A_A") (pintype "passive"))
      (node (ref "D157") (pin "A") (pinfunction "A_A") (pintype "passive"))
      (node (ref "J405") (pin "7") (pinfunction "7_7") (pintype "passive"))
      (node (ref "R4") (pin "6") (pinfunction "2_6") (pintype "passive"))
    )
    (net (code "40") (name "/Q16") (class "Default")
      (node (ref "D014") (pin "A") (pinfunction "A_A") (pintype "passive"))
      (node (ref "D028") (pin "A") (pinfunction "A_A") (pintype "passive"))
      (node (ref "D041") (pin "A") (pinfunction "A_A") (pintype "passive"))
      (node (ref "D053") (pin "A") (pinfunction "A_A") (pintype "passive"))
      (node (ref "D104") (pin "A") (pinfunction "A_A") (pintype "passive"))
      (node (ref "D114") (pin "A") (pinfunction "A_A") (pintype "passive"))
      (node (ref "D123") (pin "A") (pinfunction "A_A") (pintype "passive"))
      (node (ref "D131") (pin "A") (pinfunction "A_A") (pintype "passive"))
      (node (ref "D138") (pin "A") (pinfunction "A_A") (pintype "passive"))
      (node (ref "D144") (pin "A") (pinfunction "A_A") (pintype "passive"))
      (node (ref "D149") (pin "A") (pinfunction "A_A") (pintype "passive"))
      (node (ref "D153") (pin "A") (pinfunction "A_A") (pintype "passive"))
      (node (ref "D156") (pin "A") (pinfunction "A_A") (pintype "passive"))
      (node (ref "D158") (pin "A") (pinfunction "A_A") (pintype "passive"))
      (node (ref "D159") (pin "A") (pinfunction "A_A") (pintype "passive"))
      (node (ref "J405") (pin "8") (pinfunction "8_8") (pintype "passive"))
      (node (ref "R4") (pin "5") (pinfunction "2_5") (pintype "passive"))
    )
    (net (code "41") (name "/RESET") (class "Default")
      (node (ref "J003") (pin "1") (pinfunction "1_1") (pintype "passive"))
      (node (ref "R413") (pin "1") (pinfunction "1_1") (pintype "passive"))
      (node (ref "S429") (pin "P$2") (pinfunction "2_P$2") (pintype "bidirectional"))
      (node (ref "U401") (pin "13") (pinfunction "~{RESET}_13") (pintype "bidirectional"))
    )
    (net (code "42") (name "/RXLED") (class "Default")
      (node (ref "D408") (pin "C") (pinfunction "C_C") (pintype "passive"))
      (node (ref "U401") (pin "8") (pinfunction "PB0(SS)_8") (pintype "bidirectional"))
    )
    (net (code "43") (name "/RX_I") (class "Default")
      (node (ref "J004") (pin "2") (pinfunction "2_2") (pintype "passive"))
      (node (ref "J501") (pin "RX") (pinfunction "RX_RX") (pintype "bidirectional"))
      (node (ref "Q501") (pin "1") (pinfunction "S_1") (pintype "passive"))
      (node (ref "R501") (pin "5") (pinfunction "2_5") (pintype "passive"))
    )
    (net (code "44") (name "/SCK") (class "Default")
      (node (ref "J003") (pin "4") (pinfunction "4_4") (pintype "passive"))
      (node (ref "U401") (pin "9") (pinfunction "PB1(SCK)_9") (pintype "bidirectional"))
    )
    (net (code "45") (name "/TXLED") (class "Default")
      (node (ref "D422") (pin "C") (pinfunction "C_C") (pintype "passive"))
      (node (ref "U401") (pin "22") (pinfunction "PD5_22") (pintype "bidirectional"))
    )
    (net (code "46") (name "/TX_O") (class "Default")
      (node (ref "J004") (pin "1") (pinfunction "1_1") (pintype "passive"))
      (node (ref "J501") (pin "TX") (pinfunction "TX_TX") (pintype "bidirectional"))
      (node (ref "Q501") (pin "4") (pinfunction "S_4") (pintype "passive"))
      (node (ref "R501") (pin "7") (pinfunction "2_7") (pintype "passive"))
    )
    (net (code "47") (name "/USBD+") (class "Default")
      (node (ref "J001") (pin "1") (pinfunction "1_1") (pintype "passive"))
      (node (ref "J002") (pin "1") (pinfunction "1_1") (pintype "passive"))
      (node (ref "R403") (pin "2") (pinfunction "1_2") (pintype "passive"))
    )
    (net (code "48") (name "/USBD-") (class "Default")
      (node (ref "J001") (pin "2") (pinfunction "2_2") (pintype "passive"))
      (node (ref "J002") (pin "2") (pinfunction "2_2") (pintype "passive"))
      (node (ref "R403") (pin "1") (pinfunction "1_1") (pintype "passive"))
    )
    (net (code "49") (name "1.8V") (class "Default")
      (node (ref "C505") (pin "1") (pinfunction "1_1") (pintype "passive"))
      (node (ref "J004") (pin "6") (pinfunction "6_6") (pintype "passive"))
      (node (ref "J501") (pin "VCC") (pinfunction "VCC_VCC") (pintype "bidirectional"))
      (node (ref "Q501") (pin "2") (pinfunction "G_2") (pintype "passive"))
      (node (ref "Q501") (pin "5") (pinfunction "G_5") (pintype "passive"))
      (node (ref "Q502") (pin "2") (pinfunction "G_2") (pintype "passive"))
      (node (ref "Q502") (pin "5") (pinfunction "G_5") (pintype "passive"))
      (node (ref "R501") (pin "2") (pinfunction "1_2") (pintype "passive"))
      (node (ref "R501") (pin "4") (pinfunction "1_4") (pintype "passive"))
      (node (ref "R502") (pin "2") (pinfunction "1_2") (pintype "passive"))
      (node (ref "R502") (pin "4") (pinfunction "1_4") (pintype "passive"))
      (node (ref "U501") (pin "5") (pinfunction "VOUT_5") (pintype "bidirectional"))
    )
    (net (code "50") (name "GND") (class "Default")
      (node (ref "C010") (pin "2") (pinfunction "2_2") (pintype "passive"))
      (node (ref "C402") (pin "1") (pinfunction "1_1") (pintype "passive"))
      (node (ref "C406") (pin "1") (pinfunction "1_1") (pintype "passive"))
      (node (ref "C416") (pin "1") (pinfunction "1_1") (pintype "passive"))
      (node (ref "C417") (pin "1") (pinfunction "1_1") (pintype "passive"))
      (node (ref "C420") (pin "2") (pinfunction "2_2") (pintype "passive"))
      (node (ref "C501") (pin "2") (pinfunction "2_2") (pintype "passive"))
      (node (ref "C504") (pin "2") (pinfunction "2_2") (pintype "passive"))
      (node (ref "C505") (pin "2") (pinfunction "2_2") (pintype "passive"))
      (node (ref "J001") (pin "4") (pinfunction "4_4") (pintype "passive"))
      (node (ref "J002") (pin "4") (pinfunction "4_4") (pintype "passive"))
      (node (ref "J003") (pin "3") (pinfunction "3_3") (pintype "passive"))
      (node (ref "J004") (pin "5") (pinfunction "5_5") (pintype "passive"))
      (node (ref "J501") (pin "GND") (pinfunction "GND_GND") (pintype "bidirectional"))
      (node (ref "JP1") (pin "P$1") (pinfunction "P$1_P$1") (pintype "bidirectional"))
      (node (ref "JP2") (pin "P$1") (pinfunction "P$1_P$1") (pintype "bidirectional"))
      (node (ref "JP3") (pin "P$1") (pinfunction "P$1_P$1") (pintype "bidirectional"))
      (node (ref "JP4") (pin "P$1") (pinfunction "P$1_P$1") (pintype "bidirectional"))
      (node (ref "R413") (pin "2") (pinfunction "1_2") (pintype "passive"))
      (node (ref "S429") (pin "P$1") (pinfunction "1_P$1") (pintype "bidirectional"))
      (node (ref "U401") (pin "15") (pinfunction "GND_15") (pintype "bidirectional"))
      (node (ref "U401") (pin "23") (pinfunction "GND_23") (pintype "bidirectional"))
      (node (ref "U401") (pin "35") (pinfunction "GND_35") (pintype "bidirectional"))
      (node (ref "U401") (pin "43") (pinfunction "GND_43") (pintype "bidirectional"))
      (node (ref "U401") (pin "5") (pinfunction "UGND_5") (pintype "bidirectional"))
      (node (ref "U501") (pin "2") (pinfunction "GND_2") (pintype "bidirectional"))
      (node (ref "Y401") (pin "2") (pinfunction "GND_2") (pintype "passive"))
      (node (ref "Y401") (pin "4") (pinfunction "GND_4") (pintype "passive"))
    )
    (net (code "51") (name "Net-(D422-PadA)") (class "Default")
      (node (ref "D422") (pin "A") (pinfunction "A_A") (pintype "passive"))
      (node (ref "R422") (pin "1") (pinfunction "1_1") (pintype "passive"))
    )
    (net (code "52") (name "Net-(R403A-2)") (class "Default")
      (node (ref "R403") (pin "4") (pinfunction "2_4") (pintype "passive"))
      (node (ref "U401") (pin "3") (pinfunction "D-_3") (pintype "bidirectional"))
    )
    (net (code "53") (name "Net-(R403B-2)") (class "Default")
      (node (ref "R403") (pin "3") (pinfunction "2_3") (pintype "passive"))
      (node (ref "U401") (pin "4") (pinfunction "D+_4") (pintype "bidirectional"))
    )
    (net (code "54") (name "Net-(R413B-2)") (class "Default")
      (node (ref "R413") (pin "3") (pinfunction "2_3") (pintype "passive"))
      (node (ref "U401") (pin "33") (pinfunction "PE2/~{HWB}_33") (pintype "bidirectional"))
    )
    (net (code "55") (name "Net-(R422B-1)") (class "Default")
      (node (ref "D408") (pin "A") (pinfunction "A_A") (pintype "passive"))
      (node (ref "R422") (pin "2") (pinfunction "1_2") (pintype "passive"))
    )
    (net (code "56") (name "Net-(U401-AREF)") (class "Default")
      (node (ref "C420") (pin "1") (pinfunction "1_1") (pintype "passive"))
      (node (ref "U401") (pin "42") (pinfunction "AREF_42") (pintype "bidirectional"))
    )
    (net (code "57") (name "Net-(U401-UCAP)") (class "Default")
      (node (ref "C406") (pin "2") (pinfunction "2_2") (pintype "passive"))
      (node (ref "U401") (pin "6") (pinfunction "UCAP_6") (pintype "bidirectional"))
    )
    (net (code "58") (name "Net-(U401-XTAL1)") (class "Default")
      (node (ref "C417") (pin "2") (pinfunction "2_2") (pintype "passive"))
      (node (ref "U401") (pin "17") (pinfunction "XTAL1_17") (pintype "bidirectional"))
      (node (ref "Y401") (pin "1") (pinfunction "1_1") (pintype "passive"))
    )
    (net (code "59") (name "Net-(U401-XTAL2)") (class "Default")
      (node (ref "C416") (pin "2") (pinfunction "2_2") (pintype "passive"))
      (node (ref "U401") (pin "16") (pinfunction "XTAL2_16") (pintype "bidirectional"))
      (node (ref "Y401") (pin "3") (pinfunction "2_3") (pintype "passive"))
    )
    (net (code "60") (name "Net-(U501-BYP)") (class "Default")
      (node (ref "C504") (pin "1") (pinfunction "1_1") (pintype "passive"))
      (node (ref "U501") (pin "4") (pinfunction "BYP_4") (pintype "bidirectional"))
    )
    (net (code "61") (name "VCC") (class "Default")
      (node (ref "C010") (pin "1") (pinfunction "1_1") (pintype "passive"))
      (node (ref "C402") (pin "2") (pinfunction "2_2") (pintype "passive"))
      (node (ref "C501") (pin "1") (pinfunction "1_1") (pintype "passive"))
      (node (ref "J001") (pin "3") (pinfunction "3_3") (pintype "passive"))
      (node (ref "J002") (pin "3") (pinfunction "3_3") (pintype "passive"))
      (node (ref "J003") (pin "2") (pinfunction "2_2") (pintype "passive"))
      (node (ref "R413") (pin "4") (pinfunction "2_4") (pintype "passive"))
      (node (ref "R422") (pin "3") (pinfunction "2_3") (pintype "passive"))
      (node (ref "R422") (pin "4") (pinfunction "2_4") (pintype "passive"))
      (node (ref "R501") (pin "1") (pinfunction "1_1") (pintype "passive"))
      (node (ref "R501") (pin "3") (pinfunction "1_3") (pintype "passive"))
      (node (ref "R502") (pin "1") (pinfunction "1_1") (pintype "passive"))
      (node (ref "R502") (pin "3") (pinfunction "1_3") (pintype "passive"))
      (node (ref "U401") (pin "14") (pinfunction "VCC_14") (pintype "bidirectional"))
      (node (ref "U401") (pin "2") (pinfunction "UVCC_2") (pintype "bidirectional"))
      (node (ref "U401") (pin "24") (pinfunction "AVCC_24") (pintype "bidirectional"))
      (node (ref "U401") (pin "34") (pinfunction "VCC_34") (pintype "bidirectional"))
      (node (ref "U401") (pin "44") (pinfunction "AVCC_44") (pintype "bidirectional"))
      (node (ref "U401") (pin "7") (pinfunction "VBUS_7") (pintype "bidirectional"))
      (node (ref "U501") (pin "1") (pinfunction "VIN_1") (pintype "bidirectional"))
      (node (ref "U501") (pin "3") (pinfunction "EN_3") (pintype "bidirectional"))
    )
  )
)
